# sw_tches_rev1_0.net
KiCad netlist of a schematic drawn in EAGLE
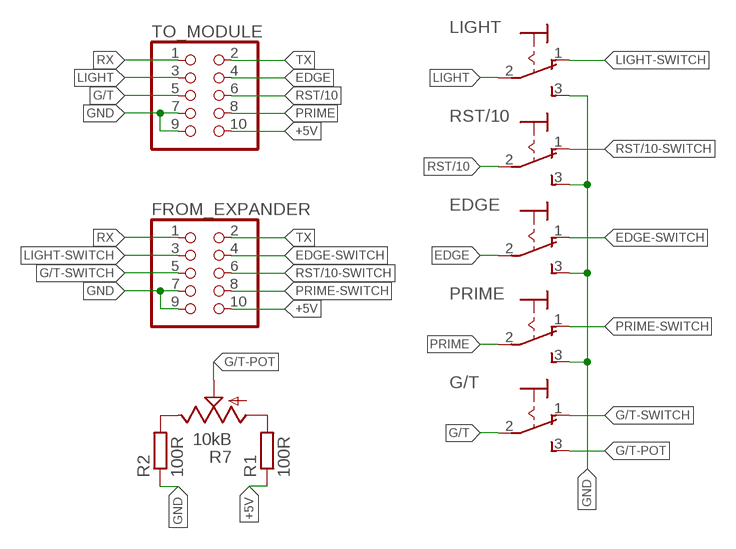
[diagram p0: schematic, sheet 1]

(export (version "E")
  (design (tool "Eeschema 10.0.6"))
  (components
    (comp (ref "EDGE")
      (value "320-916320-916BIG")
      (footprint "eagle-import:320-916MY")
      (libsource (lib "eagle-import") (part "320-916320-916BIG"))
    )
    (comp (ref "FROM_EXPANDER")
      (value "PINHD-2X5")
      (footprint "eagle-import:2X05")
      (libsource (lib "eagle-import") (part "PINHD-2X5"))
    )
    (comp (ref "G/T")
      (value "320-916320-916BIG")
      (footprint "eagle-import:320-916MY")
      (libsource (lib "eagle-import") (part "320-916320-916BIG"))
    )
    (comp (ref "LIGHT")
      (value "320-916320-916BIG")
      (footprint "eagle-import:320-916MY")
      (libsource (lib "eagle-import") (part "320-916320-916BIG"))
    )
    (comp (ref "PRIME")
      (value "320-916320-916BIG")
      (footprint "eagle-import:320-916MY")
      (libsource (lib "eagle-import") (part "320-916320-916BIG"))
    )
    (comp (ref "R1")
      (value "100R")
      (footprint "eagle-import:0204_7")
      (libsource (lib "eagle-import") (part "R-EU_0204/7"))
    )
    (comp (ref "R2")
      (value "100R")
      (footprint "eagle-import:0204_7")
      (libsource (lib "eagle-import") (part "R-EU_0204/7"))
    )
    (comp (ref "R7")
      (value "10kB")
      (footprint "eagle-import:ALPS_POT_VERTICAL_PS")
      (libsource (lib "eagle-import") (part "POT_USVERTICAL_PS"))
    )
    (comp (ref "RST/10")
      (value "320-916320-916BIG")
      (footprint "eagle-import:320-916MY")
      (libsource (lib "eagle-import") (part "320-916320-916BIG"))
    )
    (comp (ref "TO_MODULE")
      (value "PINHD-2X5")
      (footprint "eagle-import:2X05")
      (libsource (lib "eagle-import") (part "PINHD-2X5"))
    )
  )
  (nets
    (net (code "1") (name "+5V") (class "Default")
      (node (ref "FROM_EXPANDER") (pin "10") (pinfunction "10_10") (pintype "passive"))
      (node (ref "R1") (pin "1") (pinfunction "1_1") (pintype "passive"))
      (node (ref "TO_MODULE") (pin "10") (pinfunction "10_10") (pintype "passive"))
    )
    (net (code "2") (name "EDGE") (class "Default")
      (node (ref "EDGE") (pin "2") (pinfunction "P_2") (pintype "passive"))
      (node (ref "TO_MODULE") (pin "4") (pinfunction "4_4") (pintype "passive"))
    )
    (net (code "3") (name "EDGE-SWITCH") (class "Default")
      (node (ref "EDGE") (pin "1") (pinfunction "O_1") (pintype "passive"))
      (node (ref "FROM_EXPANDER") (pin "4") (pinfunction "4_4") (pintype "passive"))
    )
    (net (code "4") (name "GND") (class "Default")
      (node (ref "EDGE") (pin "3") (pinfunction "S_3") (pintype "passive"))
      (node (ref "FROM_EXPANDER") (pin "7") (pinfunction "7_7") (pintype "passive"))
      (node (ref "FROM_EXPANDER") (pin "9") (pinfunction "9_9") (pintype "passive"))
      (node (ref "LIGHT") (pin "3") (pinfunction "S_3") (pintype "passive"))
      (node (ref "PRIME") (pin "3") (pinfunction "S_3") (pintype "passive"))
      (node (ref "R2") (pin "1") (pinfunction "1_1") (pintype "passive"))
      (node (ref "RST/10") (pin "3") (pinfunction "S_3") (pintype "passive"))
      (node (ref "TO_MODULE") (pin "7") (pinfunction "7_7") (pintype "passive"))
      (node (ref "TO_MODULE") (pin "9") (pinfunction "9_9") (pintype "passive"))
    )
    (net (code "5") (name "G{slash}T") (class "Default")
      (node (ref "G/T") (pin "2") (pinfunction "P_2") (pintype "passive"))
      (node (ref "TO_MODULE") (pin "5") (pinfunction "5_5") (pintype "passive"))
    )
    (net (code "6") (name "G{slash}T-POT") (class "Default")
      (node (ref "G/T") (pin "3") (pinfunction "S_3") (pintype "passive"))
      (node (ref "R7") (pin "P$2") (pinfunction "S_P$2") (pintype "passive"))
    )
    (net (code "7") (name "G{slash}T-SWITCH") (class "Default")
      (node (ref "FROM_EXPANDER") (pin "5") (pinfunction "5_5") (pintype "passive"))
      (node (ref "G/T") (pin "1") (pinfunction "O_1") (pintype "passive"))
    )
    (net (code "8") (name "LIGHT") (class "Default")
      (node (ref "LIGHT") (pin "2") (pinfunction "P_2") (pintype "passive"))
      (node (ref "TO_MODULE") (pin "3") (pinfunction "3_3") (pintype "passive"))
    )
    (net (code "9") (name "LIGHT-SWITCH") (class "Default")
      (node (ref "FROM_EXPANDER") (pin "3") (pinfunction "3_3") (pintype "passive"))
      (node (ref "LIGHT") (pin "1") (pinfunction "O_1") (pintype "passive"))
    )
    (net (code "10") (name "Net-(R7-A)") (class "Default")
      (node (ref "R1") (pin "2") (pinfunction "2_2") (pintype "passive"))
      (node (ref "R7") (pin "P$3") (pinfunction "A_P$3") (pintype "passive"))
    )
    (net (code "11") (name "Net-(R7-E)") (class "Default")
      (node (ref "R2") (pin "2") (pinfunction "2_2") (pintype "passive"))
      (node (ref "R7") (pin "P$1") (pinfunction "E_P$1") (pintype "passive"))
    )
    (net (code "12") (name "PRIME") (class "Default")
      (node (ref "PRIME") (pin "2") (pinfunction "P_2") (pintype "passive"))
      (node (ref "TO_MODULE") (pin "8") (pinfunction "8_8") (pintype "passive"))
    )
    (net (code "13") (name "PRIME-SWITCH") (class "Default")
      (node (ref "FROM_EXPANDER") (pin "8") (pinfunction "8_8") (pintype "passive"))
      (node (ref "PRIME") (pin "1") (pinfunction "O_1") (pintype "passive"))
    )
    (net (code "14") (name "RST{slash}10") (class "Default")
      (node (ref "RST/10") (pin "2") (pinfunction "P_2") (pintype "passive"))
      (node (ref "TO_MODULE") (pin "6") (pinfunction "6_6") (pintype "passive"))
    )
    (net (code "15") (name "RST{slash}10-SWITCH") (class "Default")
      (node (ref "FROM_EXPANDER") (pin "6") (pinfunction "6_6") (pintype "passive"))
      (node (ref "RST/10") (pin "1") (pinfunction "O_1") (pintype "passive"))
    )
    (net (code "16") (name "RX") (class "Default")
      (node (ref "FROM_EXPANDER") (pin "1") (pinfunction "1_1") (pintype "passive"))
      (node (ref "TO_MODULE") (pin "1") (pinfunction "1_1") (pintype "passive"))
    )
    (net (code "17") (name "TX") (class "Default")
      (node (ref "FROM_EXPANDER") (pin "2") (pinfunction "2_2") (pintype "passive"))
      (node (ref "TO_MODULE") (pin "2") (pinfunction "2_2") (pintype "passive"))
    )
  )
)
